# shifts.net
KiCad netlist of a schematic drawn in EAGLE
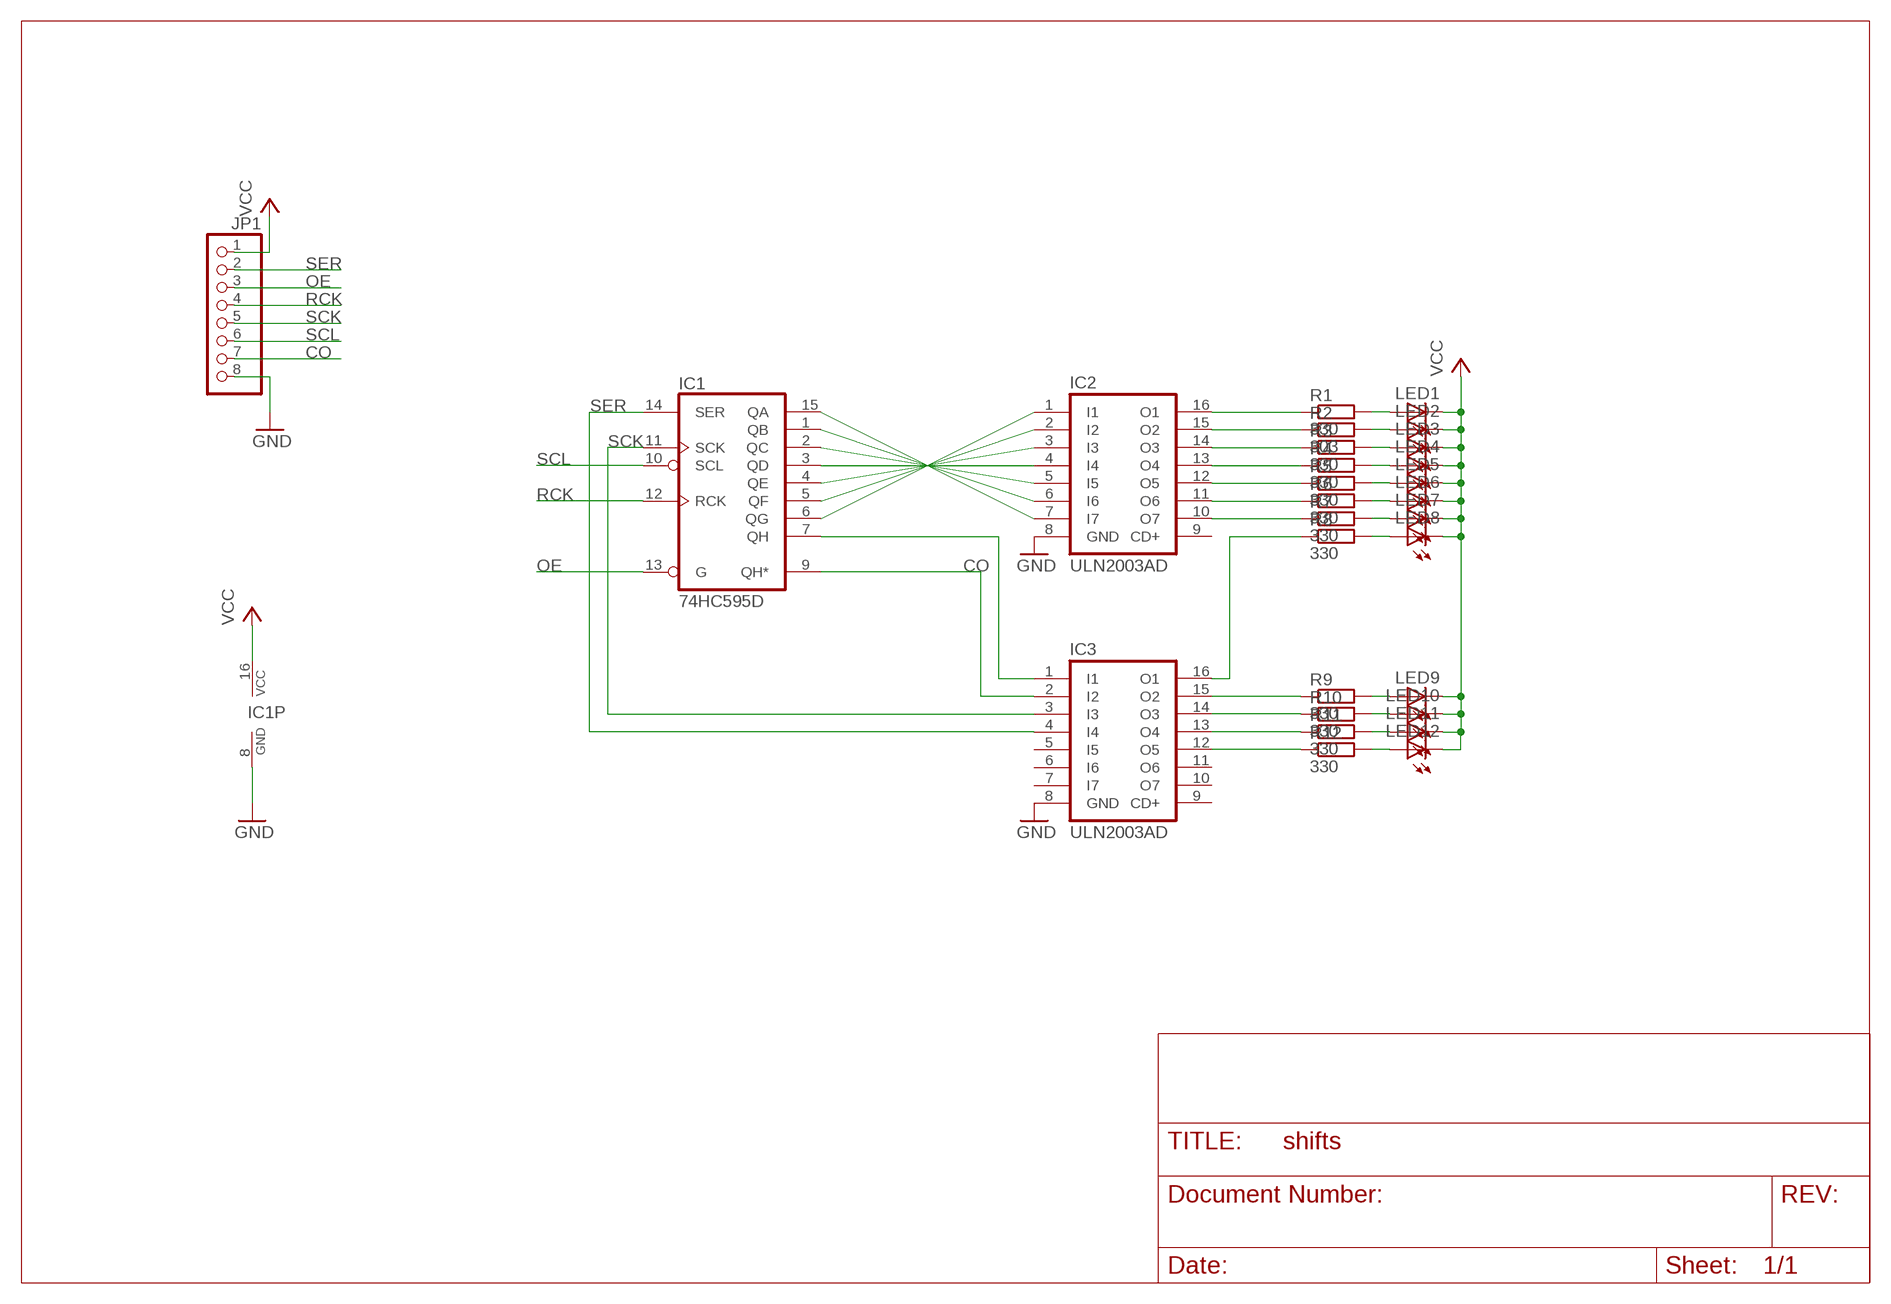
[diagram p0: schematic, sheet 1]

(export (version "E")
  (design (tool "Eeschema 10.0.6"))
  (components
    (comp (ref "IC1")
      (value "74HC595D")
      (footprint "eagle-import:SO16")
      (libsource (lib "eagle-import") (part "74595DHC"))
    )
    (comp (ref "IC2")
      (value "ULN2003AD")
      (footprint "eagle-import:SO16")
      (libsource (lib "eagle-import") (part "ULN2003AD"))
    )
    (comp (ref "IC3")
      (value "ULN2003AD")
      (footprint "eagle-import:SO16")
      (libsource (lib "eagle-import") (part "ULN2003AD"))
    )
    (comp (ref "JP1")
      (value "PINHD-1X8BIG")
      (footprint "eagle-import:1X08-BIG")
      (libsource (lib "eagle-import") (part "PINHD-1X8BIG"))
    )
    (comp (ref "LED1")
      (value "LEDCHIP-LED0805")
      (footprint "eagle-import:CHIP-LED0805")
      (libsource (lib "eagle-import") (part "LEDCHIP-LED0805"))
    )
    (comp (ref "LED2")
      (value "LEDCHIP-LED0805")
      (footprint "eagle-import:CHIP-LED0805")
      (libsource (lib "eagle-import") (part "LEDCHIP-LED0805"))
    )
    (comp (ref "LED3")
      (value "LEDCHIP-LED0805")
      (footprint "eagle-import:CHIP-LED0805")
      (libsource (lib "eagle-import") (part "LEDCHIP-LED0805"))
    )
    (comp (ref "LED4")
      (value "LEDCHIP-LED0805")
      (footprint "eagle-import:CHIP-LED0805")
      (libsource (lib "eagle-import") (part "LEDCHIP-LED0805"))
    )
    (comp (ref "LED5")
      (value "LEDCHIP-LED0805")
      (footprint "eagle-import:CHIP-LED0805")
      (libsource (lib "eagle-import") (part "LEDCHIP-LED0805"))
    )
    (comp (ref "LED6")
      (value "LEDCHIP-LED0805")
      (footprint "eagle-import:CHIP-LED0805")
      (libsource (lib "eagle-import") (part "LEDCHIP-LED0805"))
    )
    (comp (ref "LED7")
      (value "LEDCHIP-LED0805")
      (footprint "eagle-import:CHIP-LED0805")
      (libsource (lib "eagle-import") (part "LEDCHIP-LED0805"))
    )
    (comp (ref "LED8")
      (value "LEDCHIP-LED0805")
      (footprint "eagle-import:CHIP-LED0805")
      (libsource (lib "eagle-import") (part "LEDCHIP-LED0805"))
    )
    (comp (ref "LED9")
      (value "LEDCHIP-LED0805")
      (footprint "eagle-import:CHIP-LED0805")
      (libsource (lib "eagle-import") (part "LEDCHIP-LED0805"))
    )
    (comp (ref "LED10")
      (value "LEDCHIP-LED0805")
      (footprint "eagle-import:CHIP-LED0805")
      (libsource (lib "eagle-import") (part "LEDCHIP-LED0805"))
    )
    (comp (ref "LED11")
      (value "LEDCHIP-LED0805")
      (footprint "eagle-import:CHIP-LED0805")
      (libsource (lib "eagle-import") (part "LEDCHIP-LED0805"))
    )
    (comp (ref "LED12")
      (value "LEDCHIP-LED0805")
      (footprint "eagle-import:CHIP-LED0805")
      (libsource (lib "eagle-import") (part "LEDCHIP-LED0805"))
    )
    (comp (ref "R1")
      (value "330")
      (footprint "eagle-import:R0805")
      (libsource (lib "eagle-import") (part "R-EU_R0805"))
    )
    (comp (ref "R2")
      (value "303")
      (footprint "eagle-import:R0805")
      (libsource (lib "eagle-import") (part "R-EU_R0805"))
    )
    (comp (ref "R3")
      (value "330")
      (footprint "eagle-import:R0805")
      (libsource (lib "eagle-import") (part "R-EU_R0805"))
    )
    (comp (ref "R4")
      (value "330")
      (footprint "eagle-import:R0805")
      (libsource (lib "eagle-import") (part "R-EU_R0805"))
    )
    (comp (ref "R5")
      (value "330")
      (footprint "eagle-import:R0805")
      (libsource (lib "eagle-import") (part "R-EU_R0805"))
    )
    (comp (ref "R6")
      (value "330")
      (footprint "eagle-import:R0805")
      (libsource (lib "eagle-import") (part "R-EU_R0805"))
    )
    (comp (ref "R7")
      (value "330")
      (footprint "eagle-import:R0805")
      (libsource (lib "eagle-import") (part "R-EU_R0805"))
    )
    (comp (ref "R8")
      (value "330")
      (footprint "eagle-import:R0805")
      (libsource (lib "eagle-import") (part "R-EU_R0805"))
    )
    (comp (ref "R9")
      (value "330")
      (footprint "eagle-import:R0805")
      (libsource (lib "eagle-import") (part "R-EU_R0805"))
    )
    (comp (ref "R10")
      (value "330")
      (footprint "eagle-import:R0805")
      (libsource (lib "eagle-import") (part "R-EU_R0805"))
    )
    (comp (ref "R11")
      (value "330")
      (footprint "eagle-import:R0805")
      (libsource (lib "eagle-import") (part "R-EU_R0805"))
    )
    (comp (ref "R12")
      (value "330")
      (footprint "eagle-import:R0805")
      (libsource (lib "eagle-import") (part "R-EU_R0805"))
    )
  )
  (nets
    (net (code "1") (name "/CO") (class "Default")
      (node (ref "IC1") (pin "9") (pinfunction "QH*_9") (pintype "tri_state"))
      (node (ref "IC3") (pin "2") (pinfunction "I2_2") (pintype "input"))
      (node (ref "JP1") (pin "7") (pinfunction "7_7") (pintype "passive"))
    )
    (net (code "2") (name "/OE") (class "Default")
      (node (ref "IC1") (pin "13") (pinfunction "G_13") (pintype "input"))
      (node (ref "JP1") (pin "3") (pinfunction "3_3") (pintype "passive"))
    )
    (net (code "3") (name "/RCK") (class "Default")
      (node (ref "IC1") (pin "12") (pinfunction "RCK_12") (pintype "input"))
      (node (ref "JP1") (pin "4") (pinfunction "4_4") (pintype "passive"))
    )
    (net (code "4") (name "/SCK") (class "Default")
      (node (ref "IC1") (pin "11") (pinfunction "SCK_11") (pintype "input"))
      (node (ref "IC3") (pin "3") (pinfunction "I3_3") (pintype "input"))
      (node (ref "JP1") (pin "5") (pinfunction "5_5") (pintype "passive"))
    )
    (net (code "5") (name "/SCL") (class "Default")
      (node (ref "IC1") (pin "10") (pinfunction "SCL_10") (pintype "input"))
      (node (ref "JP1") (pin "6") (pinfunction "6_6") (pintype "passive"))
    )
    (net (code "6") (name "/SER") (class "Default")
      (node (ref "IC1") (pin "14") (pinfunction "SER_14") (pintype "input"))
      (node (ref "IC3") (pin "4") (pinfunction "I4_4") (pintype "input"))
      (node (ref "JP1") (pin "2") (pinfunction "2_2") (pintype "passive"))
    )
    (net (code "7") (name "GND") (class "Default")
      (node (ref "IC1") (pin "8") (pinfunction "GND_8") (pintype "power_in"))
      (node (ref "IC2") (pin "8") (pinfunction "GND_8") (pintype "power_in"))
      (node (ref "IC3") (pin "8") (pinfunction "GND_8") (pintype "power_in"))
      (node (ref "JP1") (pin "8") (pinfunction "8_8") (pintype "passive"))
    )
    (net (code "8") (name "Net-(IC1A-QA)") (class "Default")
      (node (ref "IC1") (pin "15") (pinfunction "QA_15") (pintype "tri_state"))
      (node (ref "IC2") (pin "7") (pinfunction "I7_7") (pintype "input"))
    )
    (net (code "9") (name "Net-(IC1A-QB)") (class "Default")
      (node (ref "IC1") (pin "1") (pinfunction "QB_1") (pintype "tri_state"))
      (node (ref "IC2") (pin "6") (pinfunction "I6_6") (pintype "input"))
    )
    (net (code "10") (name "Net-(IC1A-QC)") (class "Default")
      (node (ref "IC1") (pin "2") (pinfunction "QC_2") (pintype "tri_state"))
      (node (ref "IC2") (pin "5") (pinfunction "I5_5") (pintype "input"))
    )
    (net (code "11") (name "Net-(IC1A-QD)") (class "Default")
      (node (ref "IC1") (pin "3") (pinfunction "QD_3") (pintype "tri_state"))
      (node (ref "IC2") (pin "4") (pinfunction "I4_4") (pintype "input"))
    )
    (net (code "12") (name "Net-(IC1A-QE)") (class "Default")
      (node (ref "IC1") (pin "4") (pinfunction "QE_4") (pintype "tri_state"))
      (node (ref "IC2") (pin "3") (pinfunction "I3_3") (pintype "input"))
    )
    (net (code "13") (name "Net-(IC1A-QF)") (class "Default")
      (node (ref "IC1") (pin "5") (pinfunction "QF_5") (pintype "tri_state"))
      (node (ref "IC2") (pin "2") (pinfunction "I2_2") (pintype "input"))
    )
    (net (code "14") (name "Net-(IC1A-QG)") (class "Default")
      (node (ref "IC1") (pin "6") (pinfunction "QG_6") (pintype "tri_state"))
      (node (ref "IC2") (pin "1") (pinfunction "I1_1") (pintype "input"))
    )
    (net (code "15") (name "Net-(IC1A-QH)") (class "Default")
      (node (ref "IC1") (pin "7") (pinfunction "QH_7") (pintype "tri_state"))
      (node (ref "IC3") (pin "1") (pinfunction "I1_1") (pintype "input"))
    )
    (net (code "16") (name "Net-(IC2-O1)") (class "Default")
      (node (ref "IC2") (pin "16") (pinfunction "O1_16") (pintype "open_collector"))
      (node (ref "R1") (pin "1") (pinfunction "1_1") (pintype "passive"))
    )
    (net (code "17") (name "Net-(IC2-O2)") (class "Default")
      (node (ref "IC2") (pin "15") (pinfunction "O2_15") (pintype "open_collector"))
      (node (ref "R2") (pin "1") (pinfunction "1_1") (pintype "passive"))
    )
    (net (code "18") (name "Net-(IC2-O3)") (class "Default")
      (node (ref "IC2") (pin "14") (pinfunction "O3_14") (pintype "open_collector"))
      (node (ref "R3") (pin "1") (pinfunction "1_1") (pintype "passive"))
    )
    (net (code "19") (name "Net-(IC2-O4)") (class "Default")
      (node (ref "IC2") (pin "13") (pinfunction "O4_13") (pintype "open_collector"))
      (node (ref "R4") (pin "1") (pinfunction "1_1") (pintype "passive"))
    )
    (net (code "20") (name "Net-(IC2-O5)") (class "Default")
      (node (ref "IC2") (pin "12") (pinfunction "O5_12") (pintype "open_collector"))
      (node (ref "R5") (pin "1") (pinfunction "1_1") (pintype "passive"))
    )
    (net (code "21") (name "Net-(IC2-O6)") (class "Default")
      (node (ref "IC2") (pin "11") (pinfunction "O6_11") (pintype "open_collector"))
      (node (ref "R6") (pin "1") (pinfunction "1_1") (pintype "passive"))
    )
    (net (code "22") (name "Net-(IC2-O7)") (class "Default")
      (node (ref "IC2") (pin "10") (pinfunction "O7_10") (pintype "open_collector"))
      (node (ref "R7") (pin "1") (pinfunction "1_1") (pintype "passive"))
    )
    (net (code "23") (name "Net-(IC3-O1)") (class "Default")
      (node (ref "IC3") (pin "16") (pinfunction "O1_16") (pintype "open_collector"))
      (node (ref "R8") (pin "1") (pinfunction "1_1") (pintype "passive"))
    )
    (net (code "24") (name "Net-(IC3-O2)") (class "Default")
      (node (ref "IC3") (pin "15") (pinfunction "O2_15") (pintype "open_collector"))
      (node (ref "R9") (pin "1") (pinfunction "1_1") (pintype "passive"))
    )
    (net (code "25") (name "Net-(IC3-O3)") (class "Default")
      (node (ref "IC3") (pin "14") (pinfunction "O3_14") (pintype "open_collector"))
      (node (ref "R10") (pin "1") (pinfunction "1_1") (pintype "passive"))
    )
    (net (code "26") (name "Net-(IC3-O4)") (class "Default")
      (node (ref "IC3") (pin "13") (pinfunction "O4_13") (pintype "open_collector"))
      (node (ref "R11") (pin "1") (pinfunction "1_1") (pintype "passive"))
    )
    (net (code "27") (name "Net-(IC3-O5)") (class "Default")
      (node (ref "IC3") (pin "12") (pinfunction "O5_12") (pintype "open_collector"))
      (node (ref "R12") (pin "1") (pinfunction "1_1") (pintype "passive"))
    )
    (net (code "28") (name "Net-(LED1-PadA)") (class "Default")
      (node (ref "LED1") (pin "A") (pinfunction "A_A") (pintype "passive"))
      (node (ref "R1") (pin "2") (pinfunction "2_2") (pintype "passive"))
    )
    (net (code "29") (name "Net-(LED2-PadA)") (class "Default")
      (node (ref "LED2") (pin "A") (pinfunction "A_A") (pintype "passive"))
      (node (ref "R2") (pin "2") (pinfunction "2_2") (pintype "passive"))
    )
    (net (code "30") (name "Net-(LED3-PadA)") (class "Default")
      (node (ref "LED3") (pin "A") (pinfunction "A_A") (pintype "passive"))
      (node (ref "R3") (pin "2") (pinfunction "2_2") (pintype "passive"))
    )
    (net (code "31") (name "Net-(LED4-PadA)") (class "Default")
      (node (ref "LED4") (pin "A") (pinfunction "A_A") (pintype "passive"))
      (node (ref "R4") (pin "2") (pinfunction "2_2") (pintype "passive"))
    )
    (net (code "32") (name "Net-(LED5-PadA)") (class "Default")
      (node (ref "LED5") (pin "A") (pinfunction "A_A") (pintype "passive"))
      (node (ref "R5") (pin "2") (pinfunction "2_2") (pintype "passive"))
    )
    (net (code "33") (name "Net-(LED6-PadA)") (class "Default")
      (node (ref "LED6") (pin "A") (pinfunction "A_A") (pintype "passive"))
      (node (ref "R6") (pin "2") (pinfunction "2_2") (pintype "passive"))
    )
    (net (code "34") (name "Net-(LED7-PadA)") (class "Default")
      (node (ref "LED7") (pin "A") (pinfunction "A_A") (pintype "passive"))
      (node (ref "R7") (pin "2") (pinfunction "2_2") (pintype "passive"))
    )
    (net (code "35") (name "Net-(LED8-PadA)") (class "Default")
      (node (ref "LED8") (pin "A") (pinfunction "A_A") (pintype "passive"))
      (node (ref "R8") (pin "2") (pinfunction "2_2") (pintype "passive"))
    )
    (net (code "36") (name "Net-(LED9-PadA)") (class "Default")
      (node (ref "LED9") (pin "A") (pinfunction "A_A") (pintype "passive"))
      (node (ref "R9") (pin "2") (pinfunction "2_2") (pintype "passive"))
    )
    (net (code "37") (name "Net-(LED10-PadA)") (class "Default")
      (node (ref "LED10") (pin "A") (pinfunction "A_A") (pintype "passive"))
      (node (ref "R10") (pin "2") (pinfunction "2_2") (pintype "passive"))
    )
    (net (code "38") (name "Net-(LED11-PadA)") (class "Default")
      (node (ref "LED11") (pin "A") (pinfunction "A_A") (pintype "passive"))
      (node (ref "R11") (pin "2") (pinfunction "2_2") (pintype "passive"))
    )
    (net (code "39") (name "Net-(LED12-PadA)") (class "Default")
      (node (ref "LED12") (pin "A") (pinfunction "A_A") (pintype "passive"))
      (node (ref "R12") (pin "2") (pinfunction "2_2") (pintype "passive"))
    )
    (net (code "40") (name "VCC") (class "Default")
      (node (ref "IC1") (pin "16") (pinfunction "VCC_16") (pintype "power_in"))
      (node (ref "JP1") (pin "1") (pinfunction "1_1") (pintype "passive"))
      (node (ref "LED1") (pin "C") (pinfunction "C_C") (pintype "passive"))
      (node (ref "LED10") (pin "C") (pinfunction "C_C") (pintype "passive"))
      (node (ref "LED11") (pin "C") (pinfunction "C_C") (pintype "passive"))
      (node (ref "LED12") (pin "C") (pinfunction "C_C") (pintype "passive"))
      (node (ref "LED2") (pin "C") (pinfunction "C_C") (pintype "passive"))
      (node (ref "LED3") (pin "C") (pinfunction "C_C") (pintype "passive"))
      (node (ref "LED4") (pin "C") (pinfunction "C_C") (pintype "passive"))
      (node (ref "LED5") (pin "C") (pinfunction "C_C") (pintype "passive"))
      (node (ref "LED6") (pin "C") (pinfunction "C_C") (pintype "passive"))
      (node (ref "LED7") (pin "C") (pinfunction "C_C") (pintype "passive"))
      (node (ref "LED8") (pin "C") (pinfunction "C_C") (pintype "passive"))
      (node (ref "LED9") (pin "C") (pinfunction "C_C") (pintype "passive"))
    )
    (net (code "41") (name "unconnected-(IC2-CD+-Pad9)") (class "Default")
      (node (ref "IC2") (pin "9") (pinfunction "CD+_9") (pintype "passive"))
    )
    (net (code "42") (name "unconnected-(IC3-CD+-Pad9)") (class "Default")
      (node (ref "IC3") (pin "9") (pinfunction "CD+_9") (pintype "passive"))
    )
    (net (code "43") (name "unconnected-(IC3-I5-Pad5)") (class "Default")
      (node (ref "IC3") (pin "5") (pinfunction "I5_5") (pintype "input"))
    )
    (net (code "44") (name "unconnected-(IC3-I6-Pad6)") (class "Default")
      (node (ref "IC3") (pin "6") (pinfunction "I6_6") (pintype "input"))
    )
    (net (code "45") (name "unconnected-(IC3-I7-Pad7)") (class "Default")
      (node (ref "IC3") (pin "7") (pinfunction "I7_7") (pintype "input"))
    )
    (net (code "46") (name "unconnected-(IC3-O6-Pad11)") (class "Default")
      (node (ref "IC3") (pin "11") (pinfunction "O6_11") (pintype "open_collector"))
    )
    (net (code "47") (name "unconnected-(IC3-O7-Pad10)") (class "Default")
      (node (ref "IC3") (pin "10") (pinfunction "O7_10") (pintype "open_collector"))
    )
  )
)
